# Power.net
KiCad netlist of a schematic drawn in Altium Designer
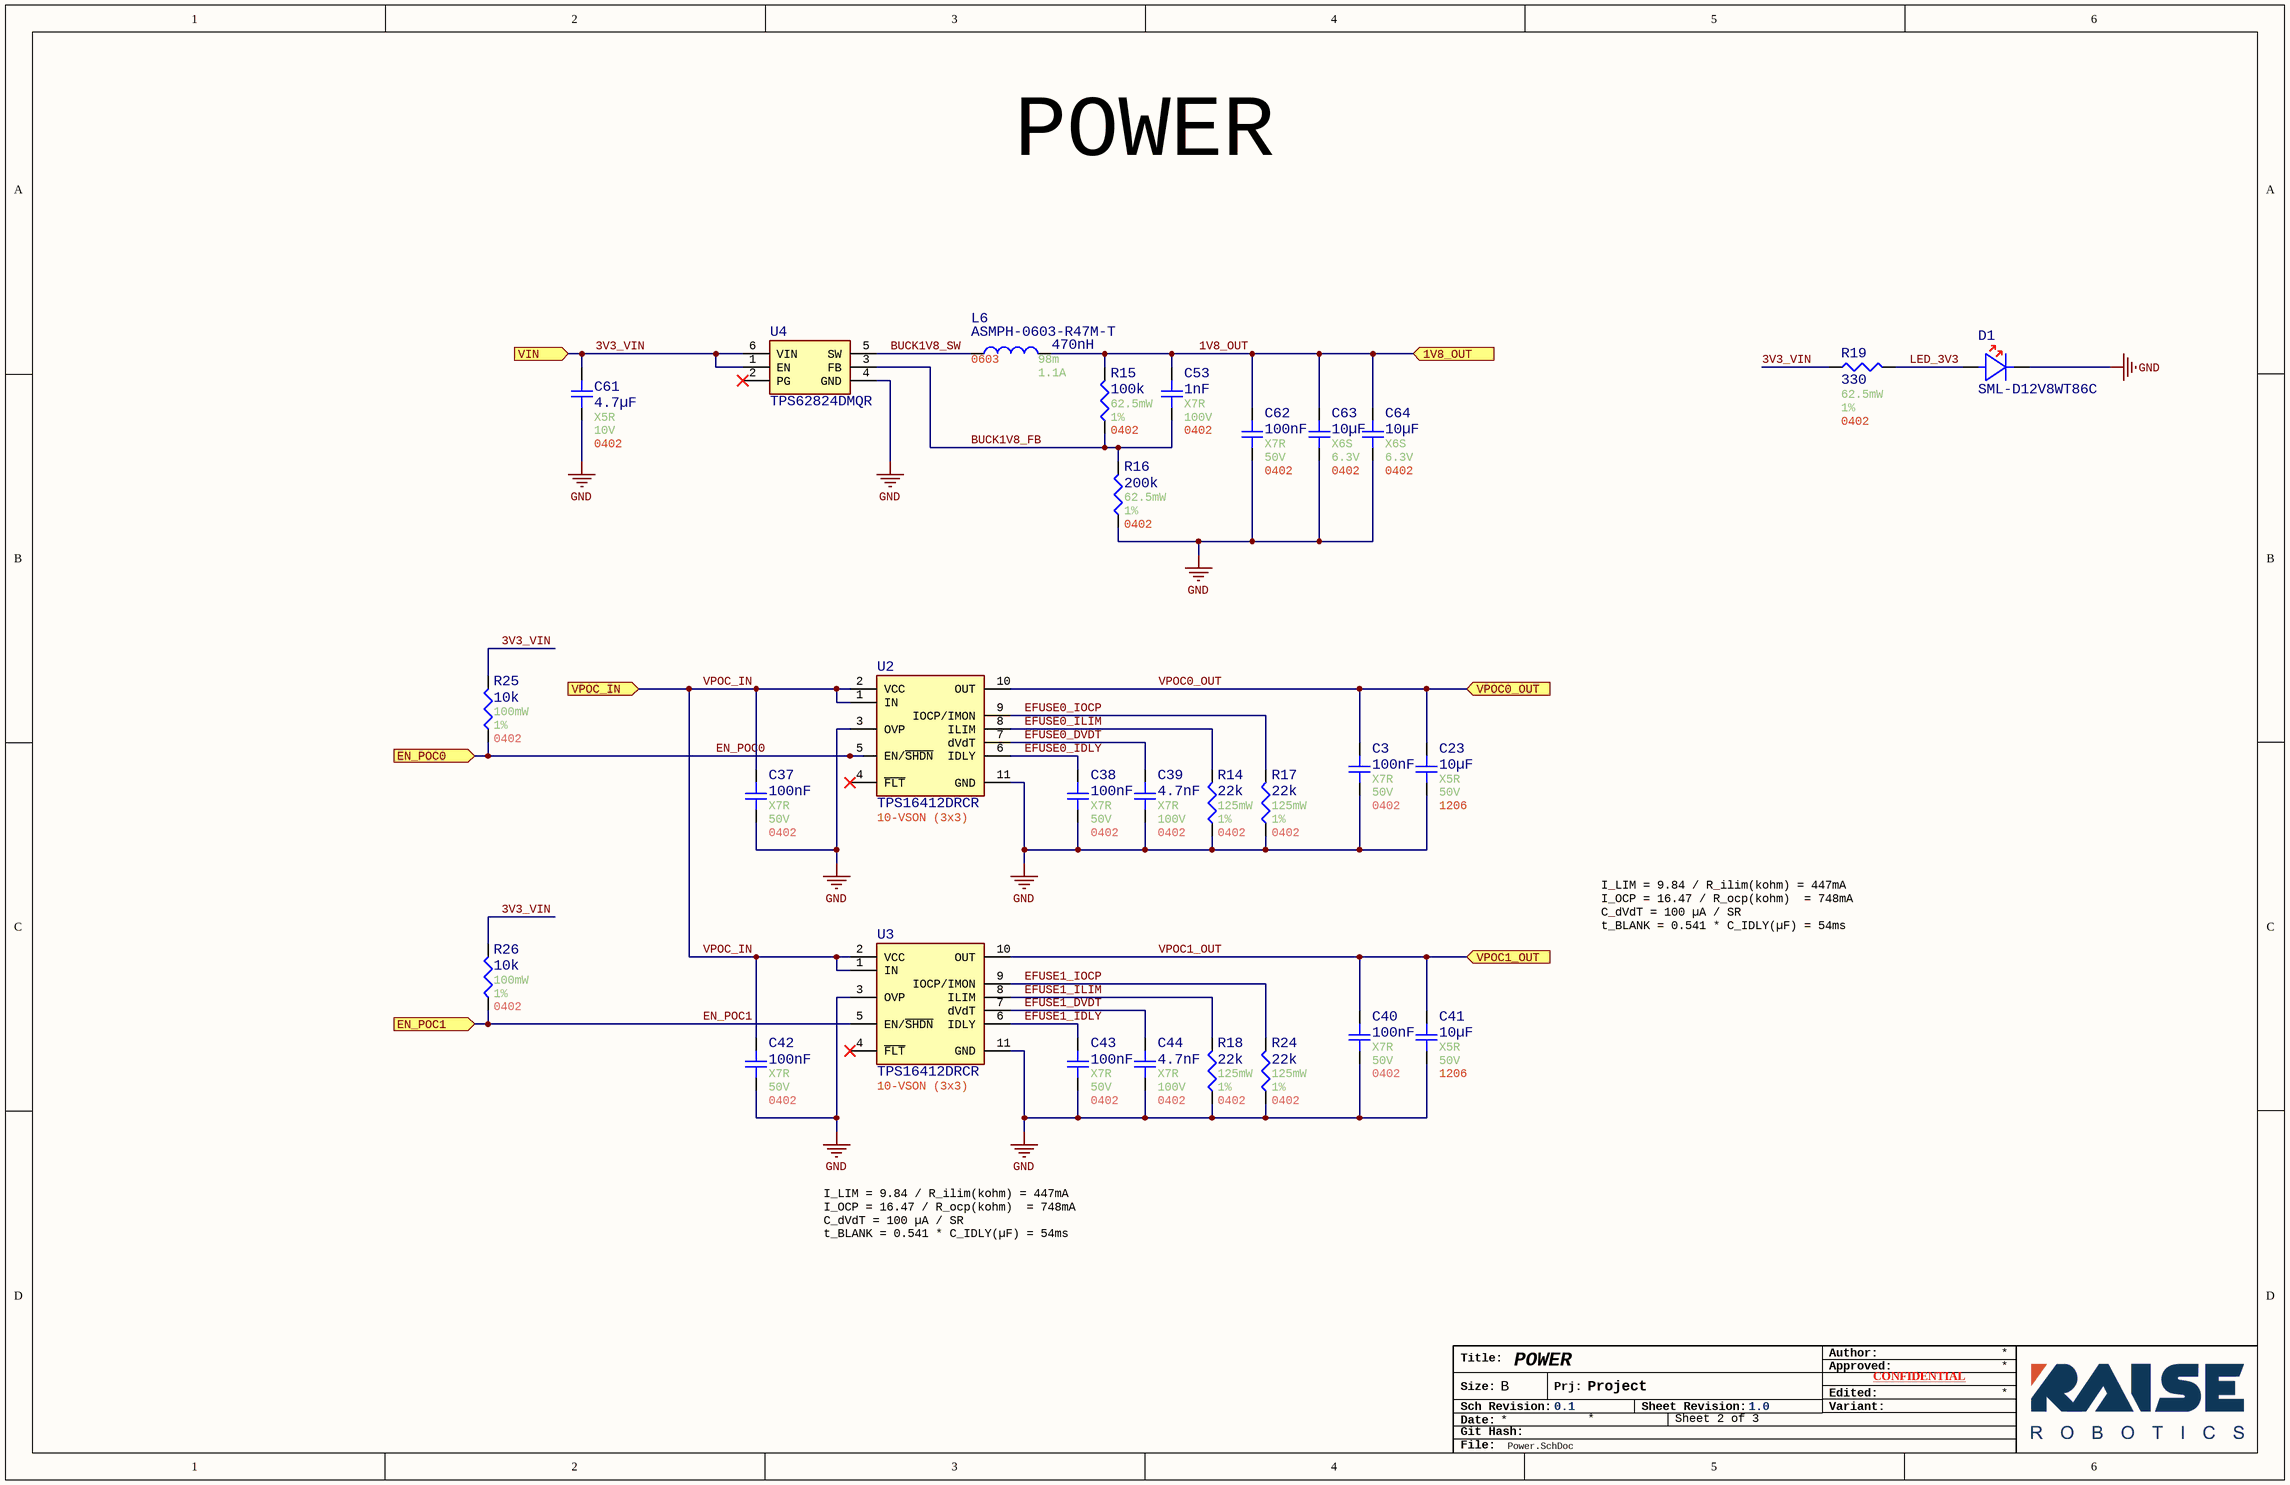
[diagram p0: Power.SchDoc]

(export (version "E")
  (design (tool "Eeschema 10.0.6"))
  (components
    (comp (ref "C3")
      (value "100nF")
      (footprint "Generic 0402 capacitor")
      (fields
        (field (name "TEMPERATURE COEFFICIENT") "X7R")
        (field (name "VOLTAGE RATING") "50V")
        (field (name "CASE/PACKAGE") "0402")
        (field (name "TOLERANCE") "10%")
        (field (name "Comment") "GRT155R71H104KE01D")
      )
      (libsource (lib "Raise Robotics") (part "Unpolarized Capacitor"))
    )
    (comp (ref "C23")
      (value "10µF")
      (footprint "Generic 1206 Capacitor")
      (fields
        (field (name "TEMPERATURE COEFFICIENT") "X5R")
        (field (name "VOLTAGE RATING") "50V")
        (field (name "CASE/PACKAGE") "1206")
        (field (name "TOLERANCE") "20%")
        (field (name "Comment") "CL31A106MBHNNNE")
      )
      (libsource (lib "Raise Robotics") (part "Unpolarized Capacitor"))
    )
    (comp (ref "C37")
      (value "100nF")
      (footprint "Generic 0402 capacitor")
      (fields
        (field (name "TEMPERATURE COEFFICIENT") "X7R")
        (field (name "VOLTAGE RATING") "50V")
        (field (name "CASE/PACKAGE") "0402")
        (field (name "TOLERANCE") "10%")
        (field (name "Comment") "GRT155R71H104KE01D")
      )
      (libsource (lib "Raise Robotics") (part "Unpolarized Capacitor"))
    )
    (comp (ref "C38")
      (value "100nF")
      (footprint "Generic 0402 capacitor")
      (fields
        (field (name "TEMPERATURE COEFFICIENT") "X7R")
        (field (name "VOLTAGE RATING") "50V")
        (field (name "CASE/PACKAGE") "0402")
        (field (name "TOLERANCE") "10%")
        (field (name "Comment") "GRT155R71H104KE01D")
      )
      (libsource (lib "Raise Robotics") (part "Unpolarized Capacitor"))
    )
    (comp (ref "C39")
      (value "4.7nF")
      (footprint "Generic 0402 capacitor")
      (fields
        (field (name "TEMPERATURE COEFFICIENT") "X7R")
        (field (name "VOLTAGE RATING") "100V")
        (field (name "CASE/PACKAGE") "0402")
        (field (name "TOLERANCE") "10%")
        (field (name "Comment") "GCM155R72A472KA37D")
      )
      (libsource (lib "Raise Robotics") (part "Unpolarized Capacitor"))
    )
    (comp (ref "C40")
      (value "100nF")
      (footprint "Generic 0402 capacitor")
      (fields
        (field (name "TEMPERATURE COEFFICIENT") "X7R")
        (field (name "VOLTAGE RATING") "50V")
        (field (name "CASE/PACKAGE") "0402")
        (field (name "TOLERANCE") "10%")
        (field (name "Comment") "GRT155R71H104KE01D")
      )
      (libsource (lib "Raise Robotics") (part "Unpolarized Capacitor"))
    )
    (comp (ref "C41")
      (value "10µF")
      (footprint "Generic 1206 Capacitor")
      (fields
        (field (name "TEMPERATURE COEFFICIENT") "X5R")
        (field (name "VOLTAGE RATING") "50V")
        (field (name "CASE/PACKAGE") "1206")
        (field (name "TOLERANCE") "20%")
        (field (name "Comment") "CL31A106MBHNNNE")
      )
      (libsource (lib "Raise Robotics") (part "Unpolarized Capacitor"))
    )
    (comp (ref "C42")
      (value "100nF")
      (footprint "Generic 0402 capacitor")
      (fields
        (field (name "TEMPERATURE COEFFICIENT") "X7R")
        (field (name "VOLTAGE RATING") "50V")
        (field (name "CASE/PACKAGE") "0402")
        (field (name "TOLERANCE") "10%")
        (field (name "Comment") "GRT155R71H104KE01D")
      )
      (libsource (lib "Raise Robotics") (part "Unpolarized Capacitor"))
    )
    (comp (ref "C43")
      (value "100nF")
      (footprint "Generic 0402 capacitor")
      (fields
        (field (name "TEMPERATURE COEFFICIENT") "X7R")
        (field (name "VOLTAGE RATING") "50V")
        (field (name "CASE/PACKAGE") "0402")
        (field (name "TOLERANCE") "10%")
        (field (name "Comment") "GRT155R71H104KE01D")
      )
      (libsource (lib "Raise Robotics") (part "Unpolarized Capacitor"))
    )
    (comp (ref "C44")
      (value "4.7nF")
      (footprint "Generic 0402 capacitor")
      (fields
        (field (name "TEMPERATURE COEFFICIENT") "X7R")
        (field (name "VOLTAGE RATING") "100V")
        (field (name "CASE/PACKAGE") "0402")
        (field (name "TOLERANCE") "10%")
        (field (name "Comment") "GCM155R72A472KA37D")
      )
      (libsource (lib "Raise Robotics") (part "Unpolarized Capacitor"))
    )
    (comp (ref "C53")
      (value "1nF")
      (footprint "Generic 0402 capacitor")
      (fields
        (field (name "TEMPERATURE COEFFICIENT") "X7R")
        (field (name "VOLTAGE RATING") "100V")
        (field (name "CASE/PACKAGE") "0402")
        (field (name "TOLERANCE") "10%")
        (field (name "Comment") "GCM155R72A102KA37J")
      )
      (libsource (lib "Raise Robotics") (part "Unpolarized Capacitor"))
    )
    (comp (ref "C61")
      (value "4.7µF")
      (footprint "Generic 0402 capacitor")
      (fields
        (field (name "TEMPERATURE COEFFICIENT") "X5R")
        (field (name "VOLTAGE RATING") "10V")
        (field (name "CASE/PACKAGE") "0402")
        (field (name "TOLERANCE") "0%")
        (field (name "Comment") "GRT155R61A475ME13D")
      )
      (libsource (lib "Raise Robotics") (part "Unpolarized Capacitor"))
    )
    (comp (ref "C62")
      (value "100nF")
      (footprint "Generic 0402 capacitor")
      (fields
        (field (name "TEMPERATURE COEFFICIENT") "X7R")
        (field (name "VOLTAGE RATING") "50V")
        (field (name "CASE/PACKAGE") "0402")
        (field (name "TOLERANCE") "10%")
        (field (name "Comment") "GRT155R71H104KE01D")
      )
      (libsource (lib "Raise Robotics") (part "Unpolarized Capacitor"))
    )
    (comp (ref "C63")
      (value "10µF")
      (footprint "Generic 0402 capacitor")
      (description "Multilayer Ceramic Capacitors MLCC - SMD/SMT 0402 10uF 6.3VDC 20% X6S AEC-Q200")
      (fields
        (field (name "TEMPERATURE COEFFICIENT") "X6S")
        (field (name "VOLTAGE RATING") "6.3V")
        (field (name "CASE/PACKAGE") "0402")
        (field (name "TOLERANCE") "20%")
        (field (name "Comment") "GRT155C80J106ME13J")
      )
      (libsource (lib "Raise Robotics") (part "Unpolarized Capacitor"))
    )
    (comp (ref "C64")
      (value "10µF")
      (footprint "Generic 0402 capacitor")
      (description "Multilayer Ceramic Capacitors MLCC - SMD/SMT 0402 10uF 6.3VDC 20% X6S AEC-Q200")
      (fields
        (field (name "TEMPERATURE COEFFICIENT") "X6S")
        (field (name "VOLTAGE RATING") "6.3V")
        (field (name "CASE/PACKAGE") "0402")
        (field (name "TOLERANCE") "20%")
        (field (name "Comment") "GRT155C80J106ME13J")
      )
      (libsource (lib "Raise Robotics") (part "Unpolarized Capacitor"))
    )
    (comp (ref "D1")
      (value "SML-D12V8WT86C")
      (footprint "FP-SML-D12-MFG")
      (description "Red 630nm LED Indication - Discrete 2.2V 0603 (1608 Metric)")
      (libsource (lib "Raise Robotics") (part "LED Red"))
    )
    (comp (ref "L6")
      (value "ASMPH-0603-R47M-T")
      (footprint "0603_1.6x0.8x0.8mm_IND")
      (description "Inductor Power Shielded Multi-Layer 0.47uH 20% 1MHz Ferrite 1.1A 0.19Ohm DCR 0603 T/R")
      (fields
        (field (name "DCR") "98m")
        (field (name "CURRENT RATING") "1.1A")
        (field (name "CASE/PACKAGE") "0603")
        (field (name "ALTIUM_VALUE") "470nH")
        (field (name "TOLERANCE") "20%")
      )
      (libsource (lib "Raise Robotics") (part "Generic 2 pin inductor"))
    )
    (comp (ref "R14")
      (value "22k")
      (footprint "Generic 0402 Resistor")
      (fields
        (field (name "POWER") "125mW")
        (field (name "TOLERANCE") "1%")
        (field (name "CASE/PACKAGE") "0402")
        (field (name "MANUFACTURER PART NUMBER") "AC0402FR-7W22KL")
      )
      (libsource (lib "Raise Robotics") (part "Resistor"))
    )
    (comp (ref "R15")
      (value "100k")
      (footprint "Generic 0402 Resistor")
      (fields
        (field (name "POWER") "62.5mW")
        (field (name "TOLERANCE") "1%")
        (field (name "CASE/PACKAGE") "0402")
        (field (name "MANUFACTURER PART NUMBER") "Blank")
        (field (name "Comment") "WR04X1003FTL")
      )
      (libsource (lib "Raise Robotics") (part "Resistor"))
    )
    (comp (ref "R16")
      (value "200k")
      (footprint "Generic 0402 Resistor")
      (description "Resistor, 200K, 0.1W, Thick Film, 0402;")
      (fields
        (field (name "POWER") "62.5mW")
        (field (name "TOLERANCE") "1%")
        (field (name "CASE/PACKAGE") "0402")
        (field (name "Comment") "560112110041")
      )
      (libsource (lib "Raise Robotics") (part "Resistor"))
    )
    (comp (ref "R17")
      (value "22k")
      (footprint "Generic 0402 Resistor")
      (fields
        (field (name "POWER") "125mW")
        (field (name "TOLERANCE") "1%")
        (field (name "CASE/PACKAGE") "0402")
        (field (name "MANUFACTURER PART NUMBER") "AC0402FR-7W22KL")
      )
      (libsource (lib "Raise Robotics") (part "Resistor"))
    )
    (comp (ref "R18")
      (value "22k")
      (footprint "Generic 0402 Resistor")
      (fields
        (field (name "POWER") "125mW")
        (field (name "TOLERANCE") "1%")
        (field (name "CASE/PACKAGE") "0402")
        (field (name "MANUFACTURER PART NUMBER") "AC0402FR-7W22KL")
      )
      (libsource (lib "Raise Robotics") (part "Resistor"))
    )
    (comp (ref "R19")
      (value "330")
      (footprint "Generic 0402 Resistor")
      (description "Res Thick Film 0402 330 Ohm 1% 0.063W ±100ppm/°C Molded SMD Paper T/R")
      (fields
        (field (name "POWER") "62.5mW")
        (field (name "TOLERANCE") "1%")
        (field (name "CASE/PACKAGE") "0402")
        (field (name "Comment") "RMCF0402FT330R")
      )
      (libsource (lib "Raise Robotics") (part "Resistor"))
    )
    (comp (ref "R24")
      (value "22k")
      (footprint "Generic 0402 Resistor")
      (fields
        (field (name "POWER") "125mW")
        (field (name "TOLERANCE") "1%")
        (field (name "CASE/PACKAGE") "0402")
        (field (name "MANUFACTURER PART NUMBER") "AC0402FR-7W22KL")
      )
      (libsource (lib "Raise Robotics") (part "Resistor"))
    )
    (comp (ref "R25")
      (value "10k")
      (footprint "Generic 0402 Resistor")
      (description "Fixed Resistor, Thin Film, 0.1W, 10000ohm, 50V, 1% +/-Tol, 100ppm/Cel, Surface Mount, 0402")
      (fields
        (field (name "POWER") "100mW")
        (field (name "TOLERANCE") "1%")
        (field (name "CASE/PACKAGE") "0402")
        (field (name "MANUFACTURER PART NUMBER") "Blank")
        (field (name "Comment") "RNCP0402FTD10K0")
      )
      (libsource (lib "Raise Robotics") (part "Resistor"))
    )
    (comp (ref "R26")
      (value "10k")
      (footprint "Generic 0402 Resistor")
      (description "Fixed Resistor, Thin Film, 0.1W, 10000ohm, 50V, 1% +/-Tol, 100ppm/Cel, Surface Mount, 0402")
      (fields
        (field (name "POWER") "100mW")
        (field (name "TOLERANCE") "1%")
        (field (name "CASE/PACKAGE") "0402")
        (field (name "MANUFACTURER PART NUMBER") "Blank")
        (field (name "Comment") "RNCP0402FTD10K0")
      )
      (libsource (lib "Raise Robotics") (part "Resistor"))
    )
    (comp (ref "U2")
      (value "TPS16412DRCR")
      (footprint "VSON-10_3x3x1.0mm_P0.5mm")
      (description "2.7-V to 40-V 152-mΩ 1.8-A eFuse with output power limiting 10-VSON -40 to 125")
      (fields (field (name "CASE/PACKAGE") "10-VSON (3x3)"))
      (libsource (lib "Raise Robotics") (part "TPS16412DRCR"))
    )
    (comp (ref "U3")
      (value "TPS16412DRCR")
      (footprint "VSON-10_3x3x1.0mm_P0.5mm")
      (description "2.7-V to 40-V 152-mΩ 1.8-A eFuse with output power limiting 10-VSON -40 to 125")
      (fields (field (name "CASE/PACKAGE") "10-VSON (3x3)"))
      (libsource (lib "Raise Robotics") (part "TPS16412DRCR"))
    )
    (comp (ref "U4")
      (value "TPS62824DMQR")
      (footprint "VSON_HR-6_1.5x1.5x1.0mm_P0.5mm")
      (description "IC REG BUCK ADJ 1A 6VSON Buck Switching Regulator IC Positive Adjustable 0.6V 1 Output 1A 6-VFDFN")
      (libsource (lib "Raise Robotics") (part "TPS62824"))
    )
  )
  (nets
    (net (code "1") (name "/1V8_OUT") (class "Default")
      (node (ref "C53") (pin "2") (pinfunction "2_2") (pintype "passive"))
      (node (ref "C62") (pin "1") (pinfunction "1_1") (pintype "passive"))
      (node (ref "C63") (pin "2") (pinfunction "2_2") (pintype "passive"))
      (node (ref "C64") (pin "2") (pinfunction "2_2") (pintype "passive"))
      (node (ref "L6") (pin "2") (pinfunction "2_2") (pintype "passive"))
      (node (ref "R15") (pin "2") (pinfunction "2_2") (pintype "passive"))
    )
    (net (code "2") (name "/3V3_VIN") (class "Default")
      (node (ref "C61") (pin "1") (pinfunction "1_1") (pintype "passive"))
      (node (ref "R19") (pin "1") (pinfunction "1_1") (pintype "passive"))
      (node (ref "R25") (pin "2") (pinfunction "2_2") (pintype "passive"))
      (node (ref "R26") (pin "2") (pinfunction "2_2") (pintype "passive"))
      (node (ref "U4") (pin "1") (pinfunction "EN_1") (pintype "passive"))
      (node (ref "U4") (pin "6") (pinfunction "VIN_6") (pintype "passive"))
    )
    (net (code "3") (name "/BUCK1V8_FB") (class "Default")
      (node (ref "C53") (pin "1") (pinfunction "1_1") (pintype "passive"))
      (node (ref "R15") (pin "1") (pinfunction "1_1") (pintype "passive"))
      (node (ref "R16") (pin "2") (pinfunction "2_2") (pintype "passive"))
      (node (ref "U4") (pin "3") (pinfunction "FB_3") (pintype "passive"))
    )
    (net (code "4") (name "/BUCK1V8_SW") (class "Default")
      (node (ref "L6") (pin "1") (pinfunction "1_1") (pintype "passive"))
      (node (ref "U4") (pin "5") (pinfunction "SW_5") (pintype "passive"))
    )
    (net (code "5") (name "/EFUSE0_DVDT") (class "Default")
      (node (ref "C39") (pin "2") (pinfunction "2_2") (pintype "passive"))
      (node (ref "U2") (pin "7") (pinfunction "dVdT_7") (pintype "passive"))
    )
    (net (code "6") (name "/EFUSE0_IDLY") (class "Default")
      (node (ref "C38") (pin "2") (pinfunction "2_2") (pintype "passive"))
      (node (ref "U2") (pin "6") (pinfunction "IDLY_6") (pintype "passive"))
    )
    (net (code "7") (name "/EFUSE0_ILIM") (class "Default")
      (node (ref "R14") (pin "2") (pinfunction "2_2") (pintype "passive"))
      (node (ref "U2") (pin "8") (pinfunction "ILIM_8") (pintype "passive"))
    )
    (net (code "8") (name "/EFUSE0_IOCP") (class "Default")
      (node (ref "R17") (pin "2") (pinfunction "2_2") (pintype "passive"))
      (node (ref "U2") (pin "9") (pinfunction "IOCP/IMON_9") (pintype "passive"))
    )
    (net (code "9") (name "/EFUSE1_DVDT") (class "Default")
      (node (ref "C44") (pin "2") (pinfunction "2_2") (pintype "passive"))
      (node (ref "U3") (pin "7") (pinfunction "dVdT_7") (pintype "passive"))
    )
    (net (code "10") (name "/EFUSE1_IDLY") (class "Default")
      (node (ref "C43") (pin "2") (pinfunction "2_2") (pintype "passive"))
      (node (ref "U3") (pin "6") (pinfunction "IDLY_6") (pintype "passive"))
    )
    (net (code "11") (name "/EFUSE1_ILIM") (class "Default")
      (node (ref "R18") (pin "2") (pinfunction "2_2") (pintype "passive"))
      (node (ref "U3") (pin "8") (pinfunction "ILIM_8") (pintype "passive"))
    )
    (net (code "12") (name "/EFUSE1_IOCP") (class "Default")
      (node (ref "R24") (pin "2") (pinfunction "2_2") (pintype "passive"))
      (node (ref "U3") (pin "9") (pinfunction "IOCP/IMON_9") (pintype "passive"))
    )
    (net (code "13") (name "/EN_POC0") (class "Default")
      (node (ref "R25") (pin "1") (pinfunction "1_1") (pintype "passive"))
      (node (ref "U2") (pin "5") (pinfunction "EN/~{SHDN}_5") (pintype "passive"))
    )
    (net (code "14") (name "/EN_POC1") (class "Default")
      (node (ref "R26") (pin "1") (pinfunction "1_1") (pintype "passive"))
      (node (ref "U3") (pin "5") (pinfunction "EN/~{SHDN}_5") (pintype "passive"))
    )
    (net (code "15") (name "/LED_3V3") (class "Default")
      (node (ref "D1") (pin "2") (pinfunction "A_2") (pintype "passive"))
      (node (ref "R19") (pin "2") (pinfunction "2_2") (pintype "passive"))
    )
    (net (code "16") (name "/VPOC0_OUT") (class "Default")
      (node (ref "C23") (pin "2") (pinfunction "2_2") (pintype "passive"))
      (node (ref "C3") (pin "2") (pinfunction "2_2") (pintype "passive"))
      (node (ref "U2") (pin "10") (pinfunction "OUT_10") (pintype "passive"))
    )
    (net (code "17") (name "/VPOC1_OUT") (class "Default")
      (node (ref "C40") (pin "2") (pinfunction "2_2") (pintype "passive"))
      (node (ref "C41") (pin "2") (pinfunction "2_2") (pintype "passive"))
      (node (ref "U3") (pin "10") (pinfunction "OUT_10") (pintype "passive"))
    )
    (net (code "18") (name "/VPOC_IN") (class "Default")
      (node (ref "C37") (pin "2") (pinfunction "2_2") (pintype "passive"))
      (node (ref "C42") (pin "2") (pinfunction "2_2") (pintype "passive"))
      (node (ref "U2") (pin "1") (pinfunction "IN_1") (pintype "passive"))
      (node (ref "U2") (pin "2") (pinfunction "VCC_2") (pintype "passive"))
      (node (ref "U3") (pin "1") (pinfunction "IN_1") (pintype "passive"))
      (node (ref "U3") (pin "2") (pinfunction "VCC_2") (pintype "passive"))
    )
    (net (code "19") (name "GND") (class "Default")
      (node (ref "C23") (pin "1") (pinfunction "1_1") (pintype "passive"))
      (node (ref "C3") (pin "1") (pinfunction "1_1") (pintype "passive"))
      (node (ref "C37") (pin "1") (pinfunction "1_1") (pintype "passive"))
      (node (ref "C38") (pin "1") (pinfunction "1_1") (pintype "passive"))
      (node (ref "C39") (pin "1") (pinfunction "1_1") (pintype "passive"))
      (node (ref "C40") (pin "1") (pinfunction "1_1") (pintype "passive"))
      (node (ref "C41") (pin "1") (pinfunction "1_1") (pintype "passive"))
      (node (ref "C42") (pin "1") (pinfunction "1_1") (pintype "passive"))
      (node (ref "C43") (pin "1") (pinfunction "1_1") (pintype "passive"))
      (node (ref "C44") (pin "1") (pinfunction "1_1") (pintype "passive"))
      (node (ref "C61") (pin "2") (pinfunction "2_2") (pintype "passive"))
      (node (ref "C62") (pin "2") (pinfunction "2_2") (pintype "passive"))
      (node (ref "C63") (pin "1") (pinfunction "1_1") (pintype "passive"))
      (node (ref "C64") (pin "1") (pinfunction "1_1") (pintype "passive"))
      (node (ref "D1") (pin "1") (pinfunction "C_1") (pintype "passive"))
      (node (ref "R14") (pin "1") (pinfunction "1_1") (pintype "passive"))
      (node (ref "R16") (pin "1") (pinfunction "1_1") (pintype "passive"))
      (node (ref "R17") (pin "1") (pinfunction "1_1") (pintype "passive"))
      (node (ref "R18") (pin "1") (pinfunction "1_1") (pintype "passive"))
      (node (ref "R24") (pin "1") (pinfunction "1_1") (pintype "passive"))
      (node (ref "U2") (pin "11") (pinfunction "GND_11") (pintype "passive"))
      (node (ref "U2") (pin "3") (pinfunction "OVP_3") (pintype "passive"))
      (node (ref "U3") (pin "11") (pinfunction "GND_11") (pintype "passive"))
      (node (ref "U3") (pin "3") (pinfunction "OVP_3") (pintype "passive"))
      (node (ref "U4") (pin "4") (pinfunction "GND_4") (pintype "passive"))
    )
    (net (code "20") (name "unconnected-(U2-~{FLT}-Pad4)") (class "Default")
      (node (ref "U2") (pin "4") (pinfunction "~{FLT}_4") (pintype "passive+no_connect"))
    )
    (net (code "21") (name "unconnected-(U3-~{FLT}-Pad4)") (class "Default")
      (node (ref "U3") (pin "4") (pinfunction "~{FLT}_4") (pintype "passive+no_connect"))
    )
    (net (code "22") (name "unconnected-(U4-PG-Pad2)") (class "Default")
      (node (ref "U4") (pin "2") (pinfunction "PG_2") (pintype "passive+no_connect"))
    )
  )
)
